# k210.net
KiCad netlist of a schematic drawn in Altium Designer
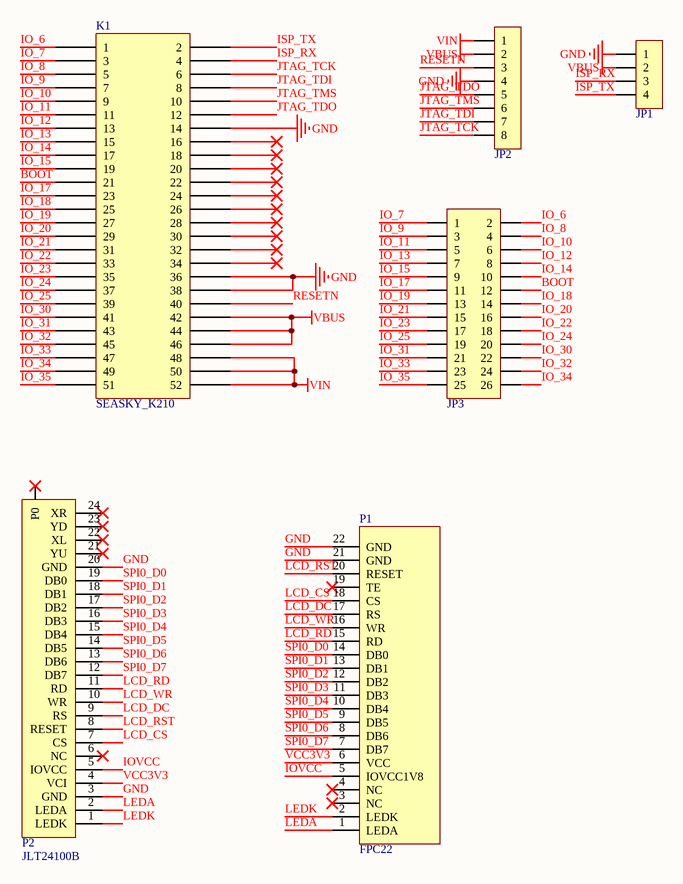
[diagram p0: k210.SchDoc]

(export (version "E")
  (design (tool "Eeschema 10.0.6"))
  (components
    (comp (ref "JP1")
      (value "HDR-1X4")
      (footprint "MX 1.25-WS-4P")
      (description "4P接插件")
      (libsource (lib "5.0 - 接插件-脚距1.25") (part "Header 4"))
    )
    (comp (ref "JP2")
      (value "HDR-1X8")
      (footprint "MX 1.25-WS-8P")
      (description "8P接插件")
      (libsource (lib "5.0 - 接插件-脚距1.25") (part "Header 8"))
    )
    (comp (ref "JP3")
      (value "Header 2X11")
      (footprint "HDR2.54-LI-2x13P")
      (description "13*2P接插件")
      (libsource (lib "5.3 - 接插件-脚距2.54 (100mil) ") (part "Header 13X2"))
    )
    (comp (ref "K1")
      (value "SEASKY_K210")
      (footprint "SEASKY_K210")
      (description "mini-PCI-E")
      (libsource (lib "Schlib1") (part "SEASKY_K210"))
    )
    (comp (ref "P1")
      (value "FPC22")
      (footprint "FPC0.5 2H-WS-22P")
      (libsource (lib "Schlib1") (part "FPC22"))
    )
    (comp (ref "P2")
      (value "JLT24100B")
      (footprint "FFC/SM0.5-2H24-LCD")
      (fields (field (name "PUBLISHER") "Altium Limited"))
      (libsource (lib "Schlib1") (part "JLT24100B"))
    )
  )
  (nets
    (net (code "1") (name "/BOOT") (class "Default")
      (node (ref "JP3") (pin "12") (pinfunction "12_12") (pintype "passive"))
      (node (ref "K1") (pin "21") (pinfunction "21_21") (pintype "passive"))
    )
    (net (code "2") (name "/IOVCC") (class "Default")
      (node (ref "P1") (pin "5") (pinfunction "IOVCC1V8_5") (pintype "passive"))
      (node (ref "P2") (pin "5") (pinfunction "IOVCC_5") (pintype "passive"))
    )
    (net (code "3") (name "/IO_6") (class "Default")
      (node (ref "JP3") (pin "2") (pinfunction "2_2") (pintype "passive"))
      (node (ref "K1") (pin "1") (pinfunction "1_1") (pintype "passive"))
    )
    (net (code "4") (name "/IO_7") (class "Default")
      (node (ref "JP3") (pin "1") (pinfunction "1_1") (pintype "passive"))
      (node (ref "K1") (pin "3") (pinfunction "3_3") (pintype "passive"))
    )
    (net (code "5") (name "/IO_8") (class "Default")
      (node (ref "JP3") (pin "4") (pinfunction "4_4") (pintype "passive"))
      (node (ref "K1") (pin "5") (pinfunction "5_5") (pintype "passive"))
    )
    (net (code "6") (name "/IO_9") (class "Default")
      (node (ref "JP3") (pin "3") (pinfunction "3_3") (pintype "passive"))
      (node (ref "K1") (pin "7") (pinfunction "7_7") (pintype "passive"))
    )
    (net (code "7") (name "/IO_10") (class "Default")
      (node (ref "JP3") (pin "6") (pinfunction "6_6") (pintype "passive"))
      (node (ref "K1") (pin "9") (pinfunction "9_9") (pintype "passive"))
    )
    (net (code "8") (name "/IO_11") (class "Default")
      (node (ref "JP3") (pin "5") (pinfunction "5_5") (pintype "passive"))
      (node (ref "K1") (pin "11") (pinfunction "11_11") (pintype "passive"))
    )
    (net (code "9") (name "/IO_12") (class "Default")
      (node (ref "JP3") (pin "8") (pinfunction "8_8") (pintype "passive"))
      (node (ref "K1") (pin "13") (pinfunction "13_13") (pintype "passive"))
    )
    (net (code "10") (name "/IO_13") (class "Default")
      (node (ref "JP3") (pin "7") (pinfunction "7_7") (pintype "passive"))
      (node (ref "K1") (pin "15") (pinfunction "15_15") (pintype "passive"))
    )
    (net (code "11") (name "/IO_14") (class "Default")
      (node (ref "JP3") (pin "10") (pinfunction "10_10") (pintype "passive"))
      (node (ref "K1") (pin "17") (pinfunction "17_17") (pintype "passive"))
    )
    (net (code "12") (name "/IO_15") (class "Default")
      (node (ref "JP3") (pin "9") (pinfunction "9_9") (pintype "passive"))
      (node (ref "K1") (pin "19") (pinfunction "19_19") (pintype "passive"))
    )
    (net (code "13") (name "/IO_17") (class "Default")
      (node (ref "JP3") (pin "11") (pinfunction "11_11") (pintype "passive"))
      (node (ref "K1") (pin "23") (pinfunction "23_23") (pintype "passive"))
    )
    (net (code "14") (name "/IO_18") (class "Default")
      (node (ref "JP3") (pin "14") (pinfunction "14_14") (pintype "passive"))
      (node (ref "K1") (pin "25") (pinfunction "25_25") (pintype "passive"))
    )
    (net (code "15") (name "/IO_19") (class "Default")
      (node (ref "JP3") (pin "13") (pinfunction "13_13") (pintype "passive"))
      (node (ref "K1") (pin "27") (pinfunction "27_27") (pintype "passive"))
    )
    (net (code "16") (name "/IO_20") (class "Default")
      (node (ref "JP3") (pin "16") (pinfunction "16_16") (pintype "passive"))
      (node (ref "K1") (pin "29") (pinfunction "29_29") (pintype "passive"))
    )
    (net (code "17") (name "/IO_21") (class "Default")
      (node (ref "JP3") (pin "15") (pinfunction "15_15") (pintype "passive"))
      (node (ref "K1") (pin "31") (pinfunction "31_31") (pintype "passive"))
    )
    (net (code "18") (name "/IO_22") (class "Default")
      (node (ref "JP3") (pin "18") (pinfunction "18_18") (pintype "passive"))
      (node (ref "K1") (pin "33") (pinfunction "33_33") (pintype "passive"))
    )
    (net (code "19") (name "/IO_23") (class "Default")
      (node (ref "JP3") (pin "17") (pinfunction "17_17") (pintype "passive"))
      (node (ref "K1") (pin "35") (pinfunction "35_35") (pintype "passive"))
    )
    (net (code "20") (name "/IO_24") (class "Default")
      (node (ref "JP3") (pin "20") (pinfunction "20_20") (pintype "passive"))
      (node (ref "K1") (pin "37") (pinfunction "37_37") (pintype "passive"))
    )
    (net (code "21") (name "/IO_25") (class "Default")
      (node (ref "JP3") (pin "19") (pinfunction "19_19") (pintype "passive"))
      (node (ref "K1") (pin "39") (pinfunction "39_39") (pintype "passive"))
    )
    (net (code "22") (name "/IO_30") (class "Default")
      (node (ref "JP3") (pin "22") (pinfunction "22_22") (pintype "passive"))
      (node (ref "K1") (pin "41") (pinfunction "41_41") (pintype "passive"))
    )
    (net (code "23") (name "/IO_31") (class "Default")
      (node (ref "JP3") (pin "21") (pinfunction "21_21") (pintype "passive"))
      (node (ref "K1") (pin "43") (pinfunction "43_43") (pintype "passive"))
    )
    (net (code "24") (name "/IO_32") (class "Default")
      (node (ref "JP3") (pin "24") (pinfunction "24_24") (pintype "passive"))
      (node (ref "K1") (pin "45") (pinfunction "45_45") (pintype "passive"))
    )
    (net (code "25") (name "/IO_33") (class "Default")
      (node (ref "JP3") (pin "23") (pinfunction "23_23") (pintype "passive"))
      (node (ref "K1") (pin "47") (pinfunction "47_47") (pintype "passive"))
    )
    (net (code "26") (name "/IO_34") (class "Default")
      (node (ref "JP3") (pin "26") (pinfunction "26_26") (pintype "passive"))
      (node (ref "K1") (pin "49") (pinfunction "49_49") (pintype "passive"))
    )
    (net (code "27") (name "/IO_35") (class "Default")
      (node (ref "JP3") (pin "25") (pinfunction "25_25") (pintype "passive"))
      (node (ref "K1") (pin "51") (pinfunction "51_51") (pintype "passive"))
    )
    (net (code "28") (name "/ISP_RX") (class "Default")
      (node (ref "JP1") (pin "3") (pinfunction "3_3") (pintype "passive"))
      (node (ref "K1") (pin "4") (pinfunction "4_4") (pintype "passive"))
    )
    (net (code "29") (name "/ISP_TX") (class "Default")
      (node (ref "JP1") (pin "4") (pinfunction "4_4") (pintype "passive"))
      (node (ref "K1") (pin "2") (pinfunction "2_2") (pintype "passive"))
    )
    (net (code "30") (name "/JTAG_TCK") (class "Default")
      (node (ref "JP2") (pin "8") (pinfunction "8_8") (pintype "passive"))
      (node (ref "K1") (pin "6") (pinfunction "6_6") (pintype "passive"))
    )
    (net (code "31") (name "/JTAG_TDI") (class "Default")
      (node (ref "JP2") (pin "7") (pinfunction "7_7") (pintype "passive"))
      (node (ref "K1") (pin "8") (pinfunction "8_8") (pintype "passive"))
    )
    (net (code "32") (name "/JTAG_TDO") (class "Default")
      (node (ref "JP2") (pin "5") (pinfunction "5_5") (pintype "passive"))
      (node (ref "K1") (pin "12") (pinfunction "12_12") (pintype "passive"))
    )
    (net (code "33") (name "/JTAG_TMS") (class "Default")
      (node (ref "JP2") (pin "6") (pinfunction "6_6") (pintype "passive"))
      (node (ref "K1") (pin "10") (pinfunction "10_10") (pintype "passive"))
    )
    (net (code "34") (name "/LCD_CS") (class "Default")
      (node (ref "P1") (pin "18") (pinfunction "CS_18") (pintype "passive"))
      (node (ref "P2") (pin "7") (pinfunction "CS_7") (pintype "passive"))
    )
    (net (code "35") (name "/LCD_DC") (class "Default")
      (node (ref "P1") (pin "17") (pinfunction "RS_17") (pintype "passive"))
      (node (ref "P2") (pin "9") (pinfunction "RS_9") (pintype "passive"))
    )
    (net (code "36") (name "/LCD_RD") (class "Default")
      (node (ref "P1") (pin "15") (pinfunction "RD_15") (pintype "passive"))
      (node (ref "P2") (pin "11") (pinfunction "RD_11") (pintype "passive"))
    )
    (net (code "37") (name "/LCD_RST") (class "Default")
      (node (ref "P1") (pin "20") (pinfunction "RESET_20") (pintype "passive"))
      (node (ref "P2") (pin "8") (pinfunction "RESET_8") (pintype "passive"))
    )
    (net (code "38") (name "/LCD_WR") (class "Default")
      (node (ref "P1") (pin "16") (pinfunction "WR_16") (pintype "passive"))
      (node (ref "P2") (pin "10") (pinfunction "WR_10") (pintype "passive"))
    )
    (net (code "39") (name "/LEDA") (class "Default")
      (node (ref "P1") (pin "1") (pinfunction "LEDA_1") (pintype "passive"))
      (node (ref "P2") (pin "2") (pinfunction "LEDA_2") (pintype "passive"))
    )
    (net (code "40") (name "/LEDK") (class "Default")
      (node (ref "P1") (pin "2") (pinfunction "LEDK_2") (pintype "passive"))
      (node (ref "P2") (pin "1") (pinfunction "LEDK_1") (pintype "passive"))
    )
    (net (code "41") (name "/RESETN") (class "Default")
      (node (ref "JP2") (pin "3") (pinfunction "3_3") (pintype "passive"))
      (node (ref "K1") (pin "40") (pinfunction "40_40") (pintype "passive"))
    )
    (net (code "42") (name "/SPI0_D0") (class "Default")
      (node (ref "P1") (pin "14") (pinfunction "DB0_14") (pintype "passive"))
      (node (ref "P2") (pin "19") (pinfunction "DB0_19") (pintype "passive"))
    )
    (net (code "43") (name "/SPI0_D1") (class "Default")
      (node (ref "P1") (pin "13") (pinfunction "DB1_13") (pintype "passive"))
      (node (ref "P2") (pin "18") (pinfunction "DB1_18") (pintype "passive"))
    )
    (net (code "44") (name "/SPI0_D2") (class "Default")
      (node (ref "P1") (pin "12") (pinfunction "DB2_12") (pintype "passive"))
      (node (ref "P2") (pin "17") (pinfunction "DB2_17") (pintype "passive"))
    )
    (net (code "45") (name "/SPI0_D3") (class "Default")
      (node (ref "P1") (pin "11") (pinfunction "DB3_11") (pintype "passive"))
      (node (ref "P2") (pin "16") (pinfunction "DB3_16") (pintype "passive"))
    )
    (net (code "46") (name "/SPI0_D4") (class "Default")
      (node (ref "P1") (pin "10") (pinfunction "DB4_10") (pintype "passive"))
      (node (ref "P2") (pin "15") (pinfunction "DB4_15") (pintype "passive"))
    )
    (net (code "47") (name "/SPI0_D5") (class "Default")
      (node (ref "P1") (pin "9") (pinfunction "DB5_9") (pintype "passive"))
      (node (ref "P2") (pin "14") (pinfunction "DB5_14") (pintype "passive"))
    )
    (net (code "48") (name "/SPI0_D6") (class "Default")
      (node (ref "P1") (pin "8") (pinfunction "DB6_8") (pintype "passive"))
      (node (ref "P2") (pin "13") (pinfunction "DB6_13") (pintype "passive"))
    )
    (net (code "49") (name "/SPI0_D7") (class "Default")
      (node (ref "P1") (pin "7") (pinfunction "DB7_7") (pintype "passive"))
      (node (ref "P2") (pin "12") (pinfunction "DB7_12") (pintype "passive"))
    )
    (net (code "50") (name "/VCC3V3") (class "Default")
      (node (ref "P1") (pin "6") (pinfunction "VCC_6") (pintype "passive"))
      (node (ref "P2") (pin "4") (pinfunction "VCI_4") (pintype "passive"))
    )
    (net (code "51") (name "GND") (class "Default")
      (node (ref "JP1") (pin "1") (pinfunction "1_1") (pintype "passive"))
      (node (ref "JP2") (pin "4") (pinfunction "4_4") (pintype "passive"))
      (node (ref "K1") (pin "14") (pinfunction "14_14") (pintype "passive"))
      (node (ref "K1") (pin "36") (pinfunction "36_36") (pintype "passive"))
      (node (ref "K1") (pin "38") (pinfunction "38_38") (pintype "passive"))
      (node (ref "P1") (pin "21") (pinfunction "GND_21") (pintype "passive"))
      (node (ref "P1") (pin "22") (pinfunction "GND_22") (pintype "passive"))
      (node (ref "P2") (pin "20") (pinfunction "GND_20") (pintype "passive"))
      (node (ref "P2") (pin "3") (pinfunction "GND_3") (pintype "passive"))
    )
    (net (code "52") (name "VBUS") (class "Default")
      (node (ref "JP1") (pin "2") (pinfunction "2_2") (pintype "passive"))
      (node (ref "JP2") (pin "2") (pinfunction "2_2") (pintype "passive"))
      (node (ref "K1") (pin "42") (pinfunction "42_42") (pintype "passive"))
      (node (ref "K1") (pin "44") (pinfunction "44_44") (pintype "passive"))
      (node (ref "K1") (pin "46") (pinfunction "46_46") (pintype "passive"))
    )
    (net (code "53") (name "VIN") (class "Default")
      (node (ref "JP2") (pin "1") (pinfunction "1_1") (pintype "passive"))
      (node (ref "K1") (pin "48") (pinfunction "48_48") (pintype "passive"))
      (node (ref "K1") (pin "50") (pinfunction "50_50") (pintype "passive"))
      (node (ref "K1") (pin "52") (pinfunction "52_52") (pintype "passive"))
    )
    (net (code "54") (name "unconnected-(K1-Pad16)") (class "Default")
      (node (ref "K1") (pin "16") (pinfunction "16_16") (pintype "passive+no_connect"))
    )
    (net (code "55") (name "unconnected-(K1-Pad18)") (class "Default")
      (node (ref "K1") (pin "18") (pinfunction "18_18") (pintype "passive+no_connect"))
    )
    (net (code "56") (name "unconnected-(K1-Pad20)") (class "Default")
      (node (ref "K1") (pin "20") (pinfunction "20_20") (pintype "passive+no_connect"))
    )
    (net (code "57") (name "unconnected-(K1-Pad22)") (class "Default")
      (node (ref "K1") (pin "22") (pinfunction "22_22") (pintype "passive+no_connect"))
    )
    (net (code "58") (name "unconnected-(K1-Pad24)") (class "Default")
      (node (ref "K1") (pin "24") (pinfunction "24_24") (pintype "passive+no_connect"))
    )
    (net (code "59") (name "unconnected-(K1-Pad26)") (class "Default")
      (node (ref "K1") (pin "26") (pinfunction "26_26") (pintype "passive+no_connect"))
    )
    (net (code "60") (name "unconnected-(K1-Pad28)") (class "Default")
      (node (ref "K1") (pin "28") (pinfunction "28_28") (pintype "passive+no_connect"))
    )
    (net (code "61") (name "unconnected-(K1-Pad30)") (class "Default")
      (node (ref "K1") (pin "30") (pinfunction "30_30") (pintype "passive+no_connect"))
    )
    (net (code "62") (name "unconnected-(K1-Pad32)") (class "Default")
      (node (ref "K1") (pin "32") (pinfunction "32_32") (pintype "passive+no_connect"))
    )
    (net (code "63") (name "unconnected-(K1-Pad34)") (class "Default")
      (node (ref "K1") (pin "34") (pinfunction "34_34") (pintype "passive+no_connect"))
    )
    (net (code "64") (name "unconnected-(P1-NC-Pad3)") (class "Default")
      (node (ref "P1") (pin "3") (pinfunction "NC_3") (pintype "passive+no_connect"))
    )
    (net (code "65") (name "unconnected-(P1-NC-Pad4)") (class "Default")
      (node (ref "P1") (pin "4") (pinfunction "NC_4") (pintype "passive+no_connect"))
    )
    (net (code "66") (name "unconnected-(P1-TE-Pad19)") (class "Default")
      (node (ref "P1") (pin "19") (pinfunction "TE_19") (pintype "passive+no_connect"))
    )
    (net (code "67") (name "unconnected-(P2-NC-Pad6)") (class "Default")
      (node (ref "P2") (pin "6") (pinfunction "NC_6") (pintype "passive+no_connect"))
    )
    (net (code "68") (name "unconnected-(P2-PadP0)") (class "Default")
      (node (ref "P2") (pin "P0") (pinfunction "P0_P0") (pintype "passive+no_connect"))
    )
    (net (code "69") (name "unconnected-(P2-XL-Pad22)") (class "Default")
      (node (ref "P2") (pin "22") (pinfunction "XL_22") (pintype "passive+no_connect"))
    )
    (net (code "70") (name "unconnected-(P2-XR-Pad24)") (class "Default")
      (node (ref "P2") (pin "24") (pinfunction "XR_24") (pintype "passive+no_connect"))
    )
    (net (code "71") (name "unconnected-(P2-YD-Pad23)") (class "Default")
      (node (ref "P2") (pin "23") (pinfunction "YD_23") (pintype "passive+no_connect"))
    )
    (net (code "72") (name "unconnected-(P2-YU-Pad21)") (class "Default")
      (node (ref "P2") (pin "21") (pinfunction "YU_21") (pintype "passive+no_connect"))
    )
  )
)
